# Goldfish-Voiceboard-based_on_fishr3.net
KiCad netlist of a schematic drawn in EAGLE
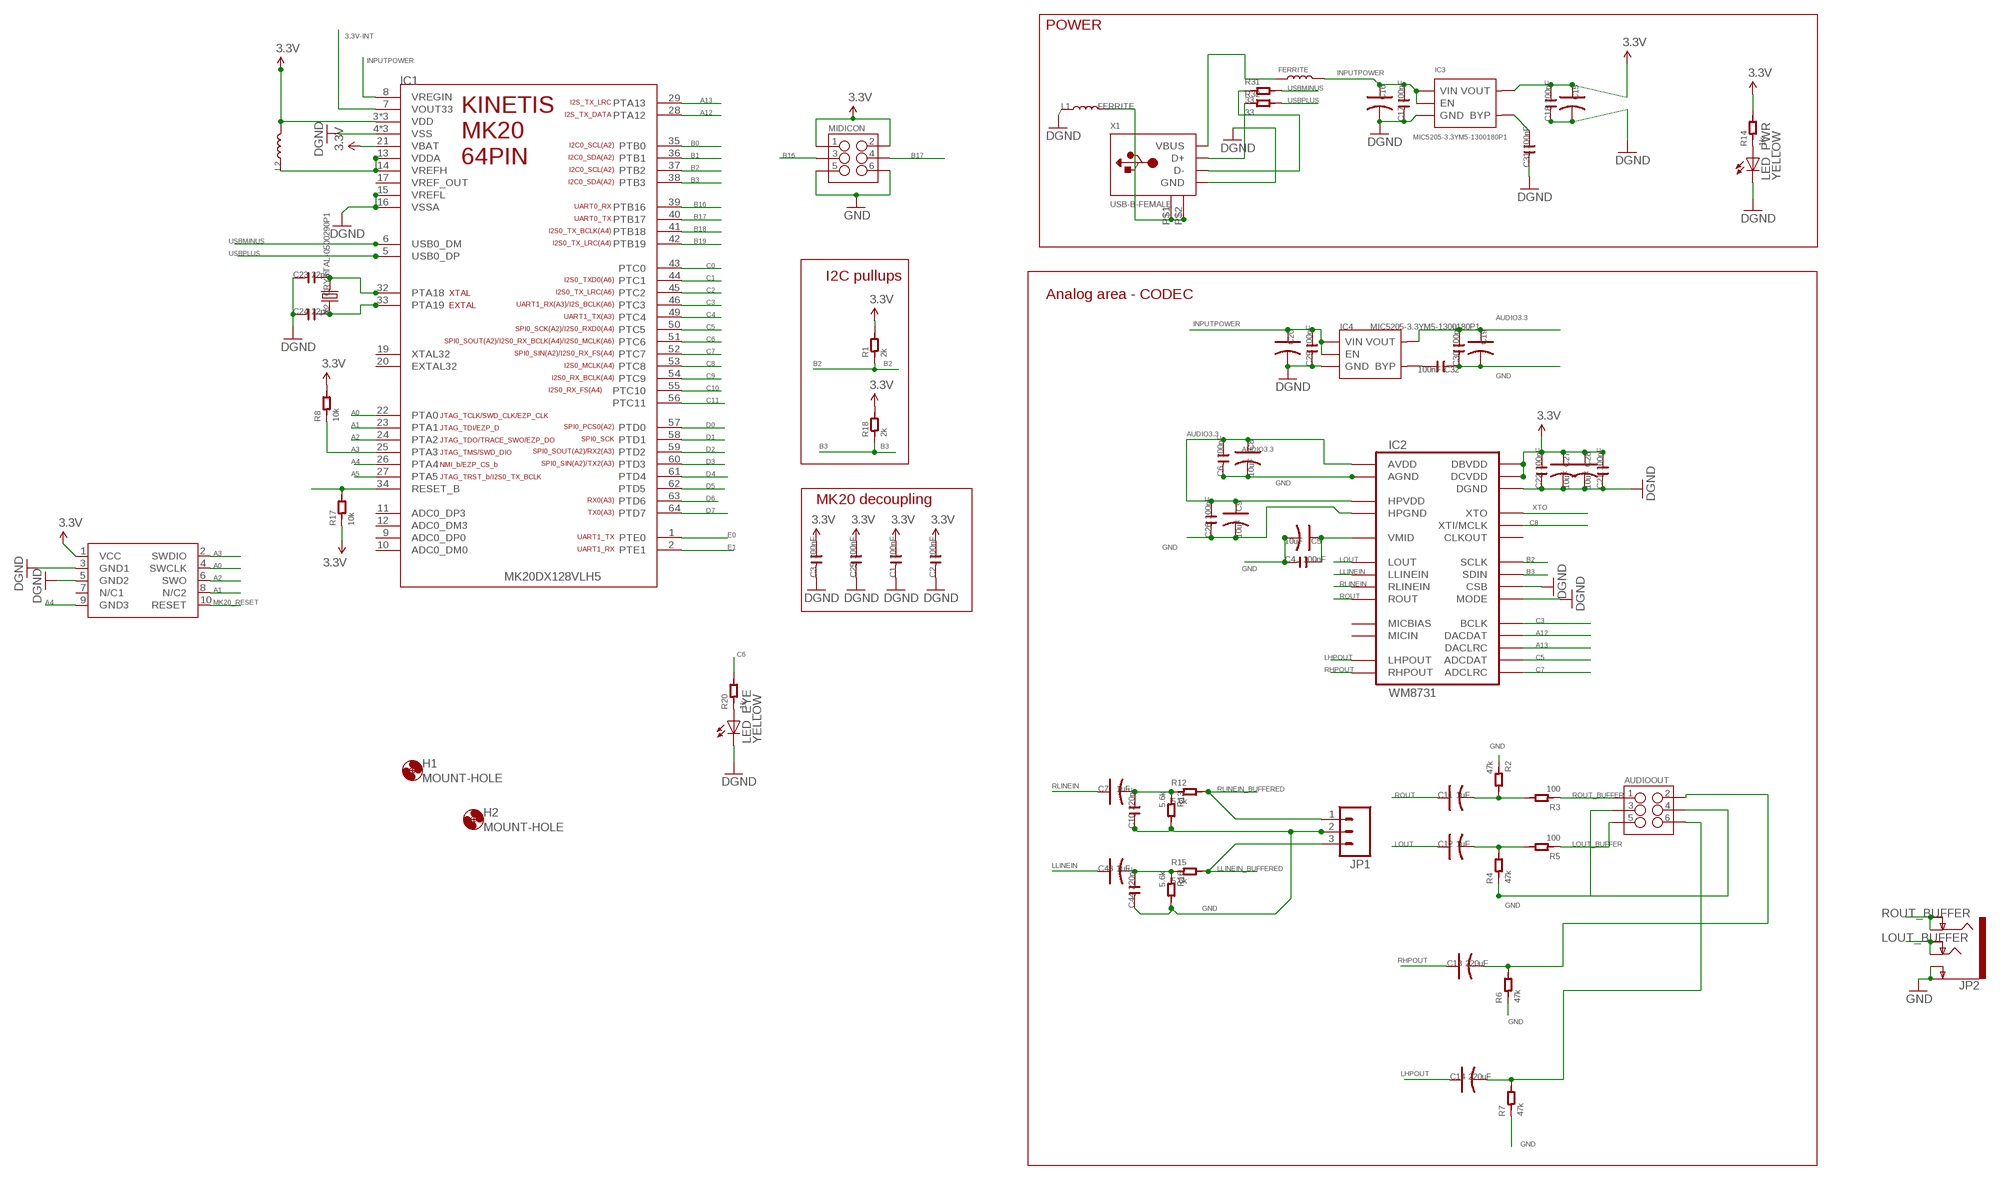
[diagram p0: schematic, sheet 1]

(export (version "E")
  (design (tool "Eeschema 10.0.6"))
  (components
    (comp (ref "AUDIOOUT")
      (value "M03X2SMT")
      (footprint "eagle-import:2X3_SMT_POSTS")
      (libsource (lib "eagle-import") (part "M03X2SMT"))
    )
    (comp (ref "C1")
      (value "100nF")
      (footprint "eagle-import:C0603")
      (libsource (lib "eagle-import") (part "C-0603"))
    )
    (comp (ref "C2")
      (value "100nF")
      (footprint "eagle-import:C0603")
      (libsource (lib "eagle-import") (part "C-0603"))
    )
    (comp (ref "C3")
      (value "100nF")
      (footprint "eagle-import:C0603")
      (libsource (lib "eagle-import") (part "C-0603"))
    )
    (comp (ref "C4")
      (value "100nF")
      (footprint "eagle-import:C0603")
      (libsource (lib "eagle-import") (part "C-0603"))
    )
    (comp (ref "C5")
      (value "10uF")
      (footprint "eagle-import:AVX-A")
      (libsource (lib "eagle-import") (part "C-POLAR-A"))
    )
    (comp (ref "C6")
      (value "100nF")
      (footprint "eagle-import:C0603")
      (libsource (lib "eagle-import") (part "C-0603"))
    )
    (comp (ref "C7")
      (value "1uF")
      (footprint "eagle-import:AVX-A")
      (libsource (lib "eagle-import") (part "C-POLAR-A"))
    )
    (comp (ref "C8")
      (value "10uF")
      (footprint "eagle-import:AVX-A")
      (libsource (lib "eagle-import") (part "C-POLAR-A"))
    )
    (comp (ref "C9")
      (value "10uF")
      (footprint "eagle-import:AVX-A")
      (libsource (lib "eagle-import") (part "C-POLAR-A"))
    )
    (comp (ref "C10")
      (value "220nF")
      (footprint "eagle-import:C0603")
      (libsource (lib "eagle-import") (part "C-0603"))
    )
    (comp (ref "C11")
      (value "1uF")
      (footprint "eagle-import:AVX-A")
      (libsource (lib "eagle-import") (part "C-POLAR-A"))
    )
    (comp (ref "C12")
      (value "1uF")
      (footprint "eagle-import:AVX-A")
      (libsource (lib "eagle-import") (part "C-POLAR-A"))
    )
    (comp (ref "C13")
      (value "220uF")
      (footprint "eagle-import:AVX-B")
      (libsource (lib "eagle-import") (part "C-POLAR-B"))
    )
    (comp (ref "C14")
      (value "220uF")
      (footprint "eagle-import:AVX-B")
      (libsource (lib "eagle-import") (part "C-POLAR-B"))
    )
    (comp (ref "C15")
      (value "C-POLAR-A")
      (footprint "eagle-import:AVX-A")
      (libsource (lib "eagle-import") (part "C-POLAR-A"))
    )
    (comp (ref "C16")
      (value "C-POLAR-A")
      (footprint "eagle-import:AVX-A")
      (libsource (lib "eagle-import") (part "C-POLAR-A"))
    )
    (comp (ref "C17")
      (value "100nF")
      (footprint "eagle-import:C0603")
      (libsource (lib "eagle-import") (part "C-0603"))
    )
    (comp (ref "C18")
      (value "100nF")
      (footprint "eagle-import:C0603")
      (libsource (lib "eagle-import") (part "C-0603"))
    )
    (comp (ref "C19")
      (value "C-POLAR-A")
      (footprint "eagle-import:AVX-A")
      (libsource (lib "eagle-import") (part "C-POLAR-A"))
    )
    (comp (ref "C20")
      (value "C-POLAR-A")
      (footprint "eagle-import:AVX-A")
      (libsource (lib "eagle-import") (part "C-POLAR-A"))
    )
    (comp (ref "C21")
      (value "100nF")
      (footprint "eagle-import:C0603")
      (libsource (lib "eagle-import") (part "C-0603"))
    )
    (comp (ref "C22")
      (value "100nF")
      (footprint "eagle-import:C0603")
      (libsource (lib "eagle-import") (part "C-0603"))
    )
    (comp (ref "C23")
      (value "22pF")
      (footprint "eagle-import:C0603")
      (libsource (lib "eagle-import") (part "C-0603"))
    )
    (comp (ref "C24")
      (value "22pF")
      (footprint "eagle-import:C0603")
      (libsource (lib "eagle-import") (part "C-0603"))
    )
    (comp (ref "C25")
      (value "100nF")
      (footprint "eagle-import:C0603")
      (libsource (lib "eagle-import") (part "C-0603"))
    )
    (comp (ref "C26")
      (value "100nF")
      (footprint "eagle-import:C0603")
      (libsource (lib "eagle-import") (part "C-0603"))
    )
    (comp (ref "C27")
      (value "10uF")
      (footprint "eagle-import:AVX-A")
      (libsource (lib "eagle-import") (part "C-POLAR-A"))
    )
    (comp (ref "C28")
      (value "10uF")
      (footprint "eagle-import:AVX-A")
      (libsource (lib "eagle-import") (part "C-POLAR-A"))
    )
    (comp (ref "C29")
      (value "100nF")
      (footprint "eagle-import:C0603")
      (libsource (lib "eagle-import") (part "C-0603"))
    )
    (comp (ref "C30")
      (value "100nF")
      (footprint "eagle-import:C0603")
      (libsource (lib "eagle-import") (part "C-0603"))
    )
    (comp (ref "C31")
      (value "100nF")
      (footprint "eagle-import:C0603")
      (libsource (lib "eagle-import") (part "C-0603"))
    )
    (comp (ref "C32")
      (value "100nF")
      (footprint "eagle-import:C0603")
      (libsource (lib "eagle-import") (part "C-0603"))
    )
    (comp (ref "C43")
      (value "1uF")
      (footprint "eagle-import:AVX-A")
      (libsource (lib "eagle-import") (part "C-POLAR-A"))
    )
    (comp (ref "C44")
      (value "220nF")
      (footprint "eagle-import:C0603")
      (libsource (lib "eagle-import") (part "C-0603"))
    )
    (comp (ref "H1")
      (value "MOUNT-HOLE")
      (footprint "eagle-import:3.2-NOMARKINGS-SMALLSAFEZONE")
      (libsource (lib "eagle-import") (part "MOUNT-HOLE"))
    )
    (comp (ref "H2")
      (value "MOUNT-HOLE")
      (footprint "eagle-import:3.2-NOMARKINGS-SMALLSAFEZONE")
      (libsource (lib "eagle-import") (part "MOUNT-HOLE"))
    )
    (comp (ref "IC1")
      (value "MK20DX128VLH5")
      (footprint "eagle-import:MK20DX128VLH5")
      (libsource (lib "eagle-import") (part "MK20DX128VLH5"))
    )
    (comp (ref "IC2")
      (value "WM8731")
      (footprint "eagle-import:28-SSOP")
      (libsource (lib "eagle-import") (part "WM8731"))
    )
    (comp (ref "IC3")
      (value "MIC5205-3.3YM5-1300180P1")
      (footprint "eagle-import:SOT23-5")
      (libsource (lib "eagle-import") (part "MIC5205-3.3YM5-1300180P1"))
    )
    (comp (ref "IC4")
      (value "MIC5205-3.3YM5-1300180P1")
      (footprint "eagle-import:SOT23-5")
      (libsource (lib "eagle-import") (part "MIC5205-3.3YM5-1300180P1"))
    )
    (comp (ref "JP1")
      (value "M03PTH")
      (footprint "eagle-import:1X03")
      (libsource (lib "eagle-import") (part "M03PTH"))
    )
    (comp (ref "JP2")
      (value "AUDIO-JACK4-.25-HORIZ-TRS")
      (footprint "eagle-import:AUDIO-JACK-.25-INCH-HORIZ-PTH")
      (libsource (lib "eagle-import") (part "AUDIO-JACK4-.25-HORIZ-TRS"))
    )
    (comp (ref "L1")
      (value "FERRITE")
      (footprint "eagle-import:L0603")
      (libsource (lib "eagle-import") (part "L-0603"))
    )
    (comp (ref "L2")
      (value "L-0603")
      (footprint "eagle-import:L0603")
      (libsource (lib "eagle-import") (part "L-0603"))
    )
    (comp (ref "L4")
      (value "FERRITE")
      (footprint "eagle-import:L0603")
      (libsource (lib "eagle-import") (part "L-0603"))
    )
    (comp (ref "LED_EYE")
      (value "YELLOW")
      (footprint "eagle-import:CHIP-LED0603")
      (libsource (lib "eagle-import") (part "LEDCHIP-LED0603"))
    )
    (comp (ref "LED_PWR")
      (value "YELLOW")
      (footprint "eagle-import:CHIP-LED0603")
      (libsource (lib "eagle-import") (part "LEDCHIP-LED0603"))
    )
    (comp (ref "MIDICON")
      (value "M03X2SMT")
      (footprint "eagle-import:2X3_SMT_POSTS")
      (libsource (lib "eagle-import") (part "M03X2SMT"))
    )
    (comp (ref "R1")
      (value "2k")
      (footprint "eagle-import:R0603")
      (libsource (lib "eagle-import") (part "R-0603"))
    )
    (comp (ref "R2")
      (value "47k")
      (footprint "eagle-import:R0603")
      (libsource (lib "eagle-import") (part "OPL Eagle Library_R-0603"))
    )
    (comp (ref "R3")
      (value "100")
      (footprint "eagle-import:R0603")
      (libsource (lib "eagle-import") (part "OPL Eagle Library_R-0603"))
    )
    (comp (ref "R4")
      (value "47k")
      (footprint "eagle-import:R0603")
      (libsource (lib "eagle-import") (part "OPL Eagle Library_R-0603"))
    )
    (comp (ref "R5")
      (value "100")
      (footprint "eagle-import:R0603")
      (libsource (lib "eagle-import") (part "OPL Eagle Library_R-0603"))
    )
    (comp (ref "R6")
      (value "47k")
      (footprint "eagle-import:R0603")
      (libsource (lib "eagle-import") (part "OPL Eagle Library_R-0603"))
    )
    (comp (ref "R7")
      (value "47k")
      (footprint "eagle-import:R0603")
      (libsource (lib "eagle-import") (part "OPL Eagle Library_R-0603"))
    )
    (comp (ref "R8")
      (value "10k")
      (footprint "eagle-import:R0603")
      (libsource (lib "eagle-import") (part "OPL Eagle Library_R-0603"))
    )
    (comp (ref "R12")
      (value "5.6k")
      (footprint "eagle-import:R0603")
      (libsource (lib "eagle-import") (part "OPL Eagle Library_R-0603"))
    )
    (comp (ref "R13")
      (value "5.6k")
      (footprint "eagle-import:R0603")
      (libsource (lib "eagle-import") (part "OPL Eagle Library_R-0603"))
    )
    (comp (ref "R14")
      (value "1k")
      (footprint "eagle-import:R0603")
      (libsource (lib "eagle-import") (part "OPL Eagle Library_R-0603"))
    )
    (comp (ref "R15")
      (value "5.6k")
      (footprint "eagle-import:R0603")
      (libsource (lib "eagle-import") (part "OPL Eagle Library_R-0603"))
    )
    (comp (ref "R16")
      (value "5.6k")
      (footprint "eagle-import:R0603")
      (libsource (lib "eagle-import") (part "OPL Eagle Library_R-0603"))
    )
    (comp (ref "R17")
      (value "10k")
      (footprint "eagle-import:R0603")
      (libsource (lib "eagle-import") (part "OPL Eagle Library_R-0603"))
    )
    (comp (ref "R18")
      (value "2k")
      (footprint "eagle-import:R0603")
      (libsource (lib "eagle-import") (part "R-0603"))
    )
    (comp (ref "R20")
      (value "1k")
      (footprint "eagle-import:R0603")
      (libsource (lib "eagle-import") (part "OPL Eagle Library_R-0603"))
    )
    (comp (ref "R31")
      (value "33")
      (footprint "eagle-import:R0603")
      (libsource (lib "eagle-import") (part "OPL Eagle Library_R-0603"))
    )
    (comp (ref "R32")
      (value "33")
      (footprint "eagle-import:R0603")
      (libsource (lib "eagle-import") (part "OPL Eagle Library_R-0603"))
    )
    (comp (ref "SWD1")
      (value "CORTEX_SWD")
      (footprint "eagle-import:M50-3600542")
      (libsource (lib "eagle-import") (part "CORTEX_SWD"))
    )
    (comp (ref "X1")
      (value "USB-B-FEMALE")
      (footprint "eagle-import:FCI61729")
      (libsource (lib "eagle-import") (part "USB-B-FEMALE"))
    )
    (comp (ref "X2")
      (value "CRYSTAL-0500290P1")
      (footprint "eagle-import:2P-SMD-5.0X3.2")
      (libsource (lib "eagle-import") (part "CRYSTAL-0500290P1"))
    )
  )
  (nets
    (net (code "1") (name "/3.3V-INT") (class "Default")
      (node (ref "IC1") (pin "7") (pinfunction "VOUT33_7") (pintype "bidirectional"))
    )
    (net (code "2") (name "/A0") (class "Default")
      (node (ref "IC1") (pin "22") (pinfunction "PTA0_22") (pintype "bidirectional"))
      (node (ref "SWD1") (pin "4") (pinfunction "SWCLK_4") (pintype "bidirectional"))
    )
    (net (code "3") (name "/A1") (class "Default")
      (node (ref "IC1") (pin "23") (pinfunction "PTA1_23") (pintype "bidirectional"))
      (node (ref "SWD1") (pin "8") (pinfunction "N/C2_8") (pintype "bidirectional"))
    )
    (net (code "4") (name "/A2") (class "Default")
      (node (ref "IC1") (pin "24") (pinfunction "PTA2_24") (pintype "bidirectional"))
      (node (ref "SWD1") (pin "6") (pinfunction "SWO_6") (pintype "bidirectional"))
    )
    (net (code "5") (name "/A3") (class "Default")
      (node (ref "IC1") (pin "25") (pinfunction "PTA3_25") (pintype "bidirectional"))
      (node (ref "R8") (pin "1") (pinfunction "1_1") (pintype "bidirectional"))
      (node (ref "SWD1") (pin "2") (pinfunction "SWDIO_2") (pintype "bidirectional"))
    )
    (net (code "6") (name "/A4") (class "Default")
      (node (ref "IC1") (pin "26") (pinfunction "PTA4_26") (pintype "bidirectional"))
      (node (ref "SWD1") (pin "9") (pinfunction "GND3_9") (pintype "bidirectional"))
    )
    (net (code "7") (name "/A5") (class "Default")
      (node (ref "IC1") (pin "27") (pinfunction "PTA5_27") (pintype "bidirectional"))
    )
    (net (code "8") (name "/A12") (class "Default")
      (node (ref "IC1") (pin "28") (pinfunction "PTA12_28") (pintype "bidirectional"))
      (node (ref "IC2") (pin "P$4") (pinfunction "DACDAT_P$4") (pintype "input"))
    )
    (net (code "9") (name "/A13") (class "Default")
      (node (ref "IC1") (pin "29") (pinfunction "PTA13_29") (pintype "bidirectional"))
      (node (ref "IC2") (pin "P$5") (pinfunction "DACLRC_P$5") (pintype "bidirectional"))
    )
    (net (code "10") (name "/AUDIO3.3") (class "Default")
      (node (ref "C19") (pin "+") (pinfunction "1_+") (pintype "bidirectional"))
      (node (ref "C26") (pin "2") (pinfunction "2_2") (pintype "bidirectional"))
      (node (ref "C30") (pin "2") (pinfunction "2_2") (pintype "bidirectional"))
      (node (ref "C6") (pin "2") (pinfunction "2_2") (pintype "bidirectional"))
      (node (ref "C8") (pin "+") (pinfunction "1_+") (pintype "bidirectional"))
      (node (ref "C9") (pin "+") (pinfunction "1_+") (pintype "bidirectional"))
      (node (ref "IC2") (pin "P$14") (pinfunction "AVDD_P$14") (pintype "power_in"))
      (node (ref "IC2") (pin "P$8") (pinfunction "HPVDD_P$8") (pintype "power_in"))
      (node (ref "IC4") (pin "5") (pinfunction "VOUT_5") (pintype "bidirectional"))
    )
    (net (code "11") (name "/B0") (class "Default")
      (node (ref "IC1") (pin "35") (pinfunction "PTB0_35") (pintype "bidirectional"))
    )
    (net (code "12") (name "/B1") (class "Default")
      (node (ref "IC1") (pin "36") (pinfunction "PTB1_36") (pintype "bidirectional"))
    )
    (net (code "13") (name "/B2") (class "Default")
      (node (ref "IC1") (pin "37") (pinfunction "PTB2_37") (pintype "bidirectional"))
      (node (ref "IC2") (pin "P$24") (pinfunction "SCLK_P$24") (pintype "input"))
      (node (ref "R1") (pin "1") (pinfunction "1_1") (pintype "bidirectional"))
    )
    (net (code "14") (name "/B3") (class "Default")
      (node (ref "IC1") (pin "38") (pinfunction "PTB3_38") (pintype "bidirectional"))
      (node (ref "IC2") (pin "P$23") (pinfunction "SDIN_P$23") (pintype "bidirectional"))
      (node (ref "R18") (pin "1") (pinfunction "1_1") (pintype "bidirectional"))
    )
    (net (code "15") (name "/B16") (class "Default")
      (node (ref "IC1") (pin "39") (pinfunction "PTB16_39") (pintype "bidirectional"))
      (node (ref "MIDICON") (pin "3") (pinfunction "3_3") (pintype "bidirectional"))
    )
    (net (code "16") (name "/B17") (class "Default")
      (node (ref "IC1") (pin "40") (pinfunction "PTB17_40") (pintype "bidirectional"))
      (node (ref "MIDICON") (pin "4") (pinfunction "4_4") (pintype "bidirectional"))
    )
    (net (code "17") (name "/B18") (class "Default")
      (node (ref "IC1") (pin "41") (pinfunction "PTB18_41") (pintype "bidirectional"))
    )
    (net (code "18") (name "/B19") (class "Default")
      (node (ref "IC1") (pin "42") (pinfunction "PTB19_42") (pintype "bidirectional"))
    )
    (net (code "19") (name "/C0") (class "Default")
      (node (ref "IC1") (pin "43") (pinfunction "PTC0_43") (pintype "bidirectional"))
    )
    (net (code "20") (name "/C1") (class "Default")
      (node (ref "IC1") (pin "44") (pinfunction "PTC1_44") (pintype "bidirectional"))
    )
    (net (code "21") (name "/C2") (class "Default")
      (node (ref "IC1") (pin "45") (pinfunction "PTC2_45") (pintype "bidirectional"))
    )
    (net (code "22") (name "/C3") (class "Default")
      (node (ref "IC1") (pin "46") (pinfunction "PTC3_46") (pintype "bidirectional"))
      (node (ref "IC2") (pin "P$3") (pinfunction "BCLK_P$3") (pintype "bidirectional"))
    )
    (net (code "23") (name "/C4") (class "Default")
      (node (ref "IC1") (pin "49") (pinfunction "PTC4_49") (pintype "bidirectional"))
    )
    (net (code "24") (name "/C5") (class "Default")
      (node (ref "IC1") (pin "50") (pinfunction "PTC5_50") (pintype "bidirectional"))
      (node (ref "IC2") (pin "P$6") (pinfunction "ADCDAT_P$6") (pintype "output"))
    )
    (net (code "25") (name "/C6") (class "Default")
      (node (ref "IC1") (pin "51") (pinfunction "PTC6_51") (pintype "bidirectional"))
      (node (ref "R20") (pin "2") (pinfunction "2_2") (pintype "bidirectional"))
    )
    (net (code "26") (name "/C7") (class "Default")
      (node (ref "IC1") (pin "52") (pinfunction "PTC7_52") (pintype "bidirectional"))
      (node (ref "IC2") (pin "P$7") (pinfunction "ADCLRC_P$7") (pintype "bidirectional"))
    )
    (net (code "27") (name "/C8") (class "Default")
      (node (ref "IC1") (pin "53") (pinfunction "PTC8_53") (pintype "bidirectional"))
      (node (ref "IC2") (pin "P$25") (pinfunction "XTI/MCLK_P$25") (pintype "input"))
    )
    (net (code "28") (name "/C9") (class "Default")
      (node (ref "IC1") (pin "54") (pinfunction "PTC9_54") (pintype "bidirectional"))
    )
    (net (code "29") (name "/C10") (class "Default")
      (node (ref "IC1") (pin "55") (pinfunction "PTC10_55") (pintype "bidirectional"))
    )
    (net (code "30") (name "/C11") (class "Default")
      (node (ref "IC1") (pin "56") (pinfunction "PTC11_56") (pintype "bidirectional"))
    )
    (net (code "31") (name "/D0") (class "Default")
      (node (ref "IC1") (pin "57") (pinfunction "PTD0_57") (pintype "bidirectional"))
    )
    (net (code "32") (name "/D1") (class "Default")
      (node (ref "IC1") (pin "58") (pinfunction "PTD1_58") (pintype "bidirectional"))
    )
    (net (code "33") (name "/D2") (class "Default")
      (node (ref "IC1") (pin "59") (pinfunction "PTD2_59") (pintype "bidirectional"))
    )
    (net (code "34") (name "/D3") (class "Default")
      (node (ref "IC1") (pin "60") (pinfunction "PTD3_60") (pintype "bidirectional"))
    )
    (net (code "35") (name "/D4") (class "Default")
      (node (ref "IC1") (pin "61") (pinfunction "PTD4_61") (pintype "bidirectional"))
    )
    (net (code "36") (name "/D5") (class "Default")
      (node (ref "IC1") (pin "62") (pinfunction "PTD5_62") (pintype "bidirectional"))
    )
    (net (code "37") (name "/D6") (class "Default")
      (node (ref "IC1") (pin "63") (pinfunction "PTD6_63") (pintype "bidirectional"))
    )
    (net (code "38") (name "/D7") (class "Default")
      (node (ref "IC1") (pin "64") (pinfunction "PTD7_64") (pintype "bidirectional"))
    )
    (net (code "39") (name "/E0") (class "Default")
      (node (ref "IC1") (pin "1") (pinfunction "PTE0_1") (pintype "bidirectional"))
    )
    (net (code "40") (name "/E1") (class "Default")
      (node (ref "IC1") (pin "2") (pinfunction "PTE1_2") (pintype "bidirectional"))
    )
    (net (code "41") (name "/INPUTPOWER") (class "Default")
      (node (ref "C16") (pin "+") (pinfunction "1_+") (pintype "bidirectional"))
      (node (ref "C17") (pin "2") (pinfunction "2_2") (pintype "bidirectional"))
      (node (ref "C20") (pin "+") (pinfunction "1_+") (pintype "bidirectional"))
      (node (ref "C29") (pin "2") (pinfunction "2_2") (pintype "bidirectional"))
      (node (ref "IC1") (pin "8") (pinfunction "VREGIN_8") (pintype "bidirectional"))
      (node (ref "IC3") (pin "1") (pinfunction "VIN_1") (pintype "bidirectional"))
      (node (ref "IC3") (pin "3") (pinfunction "EN_3") (pintype "bidirectional"))
      (node (ref "IC4") (pin "1") (pinfunction "VIN_1") (pintype "bidirectional"))
      (node (ref "IC4") (pin "3") (pinfunction "EN_3") (pintype "bidirectional"))
      (node (ref "L4") (pin "2") (pinfunction "2_2") (pintype "passive"))
    )
    (net (code "42") (name "/LHPOUT") (class "Default")
      (node (ref "C14") (pin "+") (pinfunction "1_+") (pintype "bidirectional"))
      (node (ref "IC2") (pin "P$9") (pinfunction "LHPOUT_P$9") (pintype "output"))
    )
    (net (code "43") (name "/LLINEIN") (class "Default")
      (node (ref "C43") (pin "+") (pinfunction "1_+") (pintype "bidirectional"))
      (node (ref "IC2") (pin "P$20") (pinfunction "LLINEIN_P$20") (pintype "input"))
    )
    (net (code "44") (name "/LLINEIN_BUFFERED") (class "Default")
      (node (ref "JP1") (pin "3") (pinfunction "3_3") (pintype "passive"))
      (node (ref "R15") (pin "2") (pinfunction "2_2") (pintype "bidirectional"))
    )
    (net (code "45") (name "/LOUT") (class "Default")
      (node (ref "C12") (pin "+") (pinfunction "1_+") (pintype "bidirectional"))
      (node (ref "IC2") (pin "P$12") (pinfunction "LOUT_P$12") (pintype "output"))
    )
    (net (code "46") (name "/LOUT_BUFFER") (class "Default")
      (node (ref "AUDIOOUT") (pin "5") (pinfunction "5_5") (pintype "bidirectional"))
      (node (ref "JP2") (pin "P$6") (pinfunction "TIP_P$6") (pintype "bidirectional"))
      (node (ref "JP2") (pin "P$7") (pinfunction "TIP-NORM_P$7") (pintype "bidirectional"))
      (node (ref "R5") (pin "1") (pinfunction "1_1") (pintype "bidirectional"))
    )
    (net (code "47") (name "/MK20_RESET") (class "Default")
      (node (ref "IC1") (pin "34") (pinfunction "RESET_B_34") (pintype "bidirectional"))
      (node (ref "R17") (pin "2") (pinfunction "2_2") (pintype "bidirectional"))
      (node (ref "SWD1") (pin "10") (pinfunction "RESET_10") (pintype "bidirectional"))
    )
    (net (code "48") (name "/RHPOUT") (class "Default")
      (node (ref "C13") (pin "+") (pinfunction "1_+") (pintype "bidirectional"))
      (node (ref "IC2") (pin "P$10") (pinfunction "RHPOUT_P$10") (pintype "output"))
    )
    (net (code "49") (name "/RLINEIN") (class "Default")
      (node (ref "C7") (pin "+") (pinfunction "1_+") (pintype "bidirectional"))
      (node (ref "IC2") (pin "P$19") (pinfunction "RLINEIN_P$19") (pintype "input"))
    )
    (net (code "50") (name "/RLINEIN_BUFFERED") (class "Default")
      (node (ref "JP1") (pin "1") (pinfunction "1_1") (pintype "passive"))
      (node (ref "R12") (pin "2") (pinfunction "2_2") (pintype "bidirectional"))
    )
    (net (code "51") (name "/ROUT") (class "Default")
      (node (ref "C11") (pin "+") (pinfunction "1_+") (pintype "bidirectional"))
      (node (ref "IC2") (pin "P$13") (pinfunction "ROUT_P$13") (pintype "output"))
    )
    (net (code "52") (name "/ROUT_BUFFER") (class "Default")
      (node (ref "AUDIOOUT") (pin "1") (pinfunction "1_1") (pintype "bidirectional"))
      (node (ref "JP2") (pin "P$4") (pinfunction "RING_P$4") (pintype "bidirectional"))
      (node (ref "JP2") (pin "P$5") (pinfunction "RING-NORM_P$5") (pintype "bidirectional"))
      (node (ref "R3") (pin "1") (pinfunction "1_1") (pintype "bidirectional"))
    )
    (net (code "53") (name "/USBMINUS") (class "Default")
      (node (ref "IC1") (pin "6") (pinfunction "USB0_DM_6") (pintype "bidirectional"))
      (node (ref "R31") (pin "2") (pinfunction "2_2") (pintype "bidirectional"))
    )
    (net (code "54") (name "/USBPLUS") (class "Default")
      (node (ref "IC1") (pin "5") (pinfunction "USB0_DP_5") (pintype "bidirectional"))
      (node (ref "R32") (pin "2") (pinfunction "2_2") (pintype "bidirectional"))
    )
    (net (code "55") (name "/XTO") (class "Default")
      (node (ref "IC2") (pin "P$26") (pinfunction "XTO_P$26") (pintype "output"))
    )
    (net (code "56") (name "3.3V") (class "Default")
      (node (ref "C1") (pin "2") (pinfunction "2_2") (pintype "bidirectional"))
      (node (ref "C15") (pin "+") (pinfunction "1_+") (pintype "bidirectional"))
      (node (ref "C18") (pin "2") (pinfunction "2_2") (pintype "bidirectional"))
      (node (ref "C2") (pin "2") (pinfunction "2_2") (pintype "bidirectional"))
      (node (ref "C21") (pin "2") (pinfunction "2_2") (pintype "bidirectional"))
      (node (ref "C22") (pin "2") (pinfunction "2_2") (pintype "bidirectional"))
      (node (ref "C25") (pin "2") (pinfunction "2_2") (pintype "bidirectional"))
      (node (ref "C27") (pin "+") (pinfunction "1_+") (pintype "bidirectional"))
      (node (ref "C28") (pin "+") (pinfunction "1_+") (pintype "bidirectional"))
      (node (ref "C3") (pin "2") (pinfunction "2_2") (pintype "bidirectional"))
      (node (ref "IC1") (pin "21") (pinfunction "VBAT_21") (pintype "bidirectional"))
      (node (ref "IC1") (pin "3") (pinfunction "VDD_3") (pintype "bidirectional"))
      (node (ref "IC1") (pin "30") (pinfunction "VDD_30") (pintype "bidirectional"))
      (node (ref "IC1") (pin "48") (pinfunction "VDD_48") (pintype "bidirectional"))
      (node (ref "IC2") (pin "P$1") (pinfunction "DBVDD_P$1") (pintype "power_in"))
      (node (ref "IC2") (pin "P$27") (pinfunction "DCVDD_P$27") (pintype "power_in"))
      (node (ref "IC3") (pin "5") (pinfunction "VOUT_5") (pintype "bidirectional"))
      (node (ref "L2") (pin "2") (pinfunction "2_2") (pintype "passive"))
      (node (ref "MIDICON") (pin "1") (pinfunction "1_1") (pintype "bidirectional"))
      (node (ref "MIDICON") (pin "2") (pinfunction "2_2") (pintype "bidirectional"))
      (node (ref "R1") (pin "2") (pinfunction "2_2") (pintype "bidirectional"))
      (node (ref "R14") (pin "2") (pinfunction "2_2") (pintype "bidirectional"))
      (node (ref "R17") (pin "1") (pinfunction "1_1") (pintype "bidirectional"))
      (node (ref "R18") (pin "2") (pinfunction "2_2") (pintype "bidirectional"))
      (node (ref "R8") (pin "2") (pinfunction "2_2") (pintype "bidirectional"))
      (node (ref "SWD1") (pin "1") (pinfunction "VCC_1") (pintype "bidirectional"))
    )
    (net (code "57") (name "DGND") (class "Default")
      (node (ref "AUDIOOUT") (pin "3") (pinfunction "3_3") (pintype "bidirectional"))
      (node (ref "AUDIOOUT") (pin "4") (pinfunction "4_4") (pintype "bidirectional"))
      (node (ref "C1") (pin "1") (pinfunction "1_1") (pintype "bidirectional"))
      (node (ref "C10") (pin "1") (pinfunction "1_1") (pintype "bidirectional"))
      (node (ref "C15") (pin "-") (pinfunction "2_-") (pintype "bidirectional"))
      (node (ref "C16") (pin "-") (pinfunction "2_-") (pintype "bidirectional"))
      (node (ref "C17") (pin "1") (pinfunction "1_1") (pintype "bidirectional"))
      (node (ref "C18") (pin "1") (pinfunction "1_1") (pintype "bidirectional"))
      (node (ref "C19") (pin "-") (pinfunction "2_-") (pintype "bidirectional"))
      (node (ref "C2") (pin "1") (pinfunction "1_1") (pintype "bidirectional"))
      (node (ref "C20") (pin "-") (pinfunction "2_-") (pintype "bidirectional"))
      (node (ref "C21") (pin "1") (pinfunction "1_1") (pintype "bidirectional"))
      (node (ref "C22") (pin "1") (pinfunction "1_1") (pintype "bidirectional"))
      (node (ref "C23") (pin "1") (pinfunction "1_1") (pintype "bidirectional"))
      (node (ref "C24") (pin "1") (pinfunction "1_1") (pintype "bidirectional"))
      (node (ref "C25") (pin "1") (pinfunction "1_1") (pintype "bidirectional"))
      (node (ref "C26") (pin "1") (pinfunction "1_1") (pintype "bidirectional"))
      (node (ref "C27") (pin "-") (pinfunction "2_-") (pintype "bidirectional"))
      (node (ref "C28") (pin "-") (pinfunction "2_-") (pintype "bidirectional"))
      (node (ref "C29") (pin "1") (pinfunction "1_1") (pintype "bidirectional"))
      (node (ref "C3") (pin "1") (pinfunction "1_1") (pintype "bidirectional"))
      (node (ref "C30") (pin "1") (pinfunction "1_1") (pintype "bidirectional"))
      (node (ref "C31") (pin "1") (pinfunction "1_1") (pintype "bidirectional"))
      (node (ref "C32") (pin "1") (pinfunction "1_1") (pintype "bidirectional"))
      (node (ref "C4") (pin "1") (pinfunction "1_1") (pintype "bidirectional"))
      (node (ref "C44") (pin "1") (pinfunction "1_1") (pintype "bidirectional"))
      (node (ref "C5") (pin "-") (pinfunction "2_-") (pintype "bidirectional"))
      (node (ref "C6") (pin "1") (pinfunction "1_1") (pintype "bidirectional"))
      (node (ref "C8") (pin "-") (pinfunction "2_-") (pintype "bidirectional"))
      (node (ref "C9") (pin "-") (pinfunction "2_-") (pintype "bidirectional"))
      (node (ref "IC1") (pin "15") (pinfunction "VREFL_15") (pintype "bidirectional"))
      (node (ref "IC1") (pin "16") (pinfunction "VSSA_16") (pintype "bidirectional"))
      (node (ref "IC1") (pin "31") (pinfunction "VSS_31") (pintype "bidirectional"))
      (node (ref "IC1") (pin "4") (pinfunction "VSS_4") (pintype "bidirectional"))
      (node (ref "IC1") (pin "47") (pinfunction "VSS_47") (pintype "bidirectional"))
      (node (ref "IC2") (pin "P$11") (pinfunction "HPGND_P$11") (pintype "power_in"))
      (node (ref "IC2") (pin "P$15") (pinfunction "AGND_P$15") (pintype "power_in"))
      (node (ref "IC2") (pin "P$21") (pinfunction "MODE_P$21") (pintype "input"))
      (node (ref "IC2") (pin "P$22") (pinfunction "CSB_P$22") (pintype "input"))
      (node (ref "IC2") (pin "P$28") (pinfunction "DGND_P$28") (pintype "power_in"))
      (node (ref "IC3") (pin "2") (pinfunction "GND_2") (pintype "bidirectional"))
      (node (ref "IC4") (pin "2") (pinfunction "GND_2") (pintype "bidirectional"))
      (node (ref "JP1") (pin "2") (pinfunction "2_2") (pintype "passive"))
      (node (ref "JP2") (pin "P$2") (pinfunction "EARTH_P$2") (pintype "bidirectional"))
      (node (ref "JP2") (pin "P$3") (pinfunction "EARTH-NORM_P$3") (pintype "bidirectional"))
      (node (ref "L1") (pin "1") (pinfunction "1_1") (pintype "passive"))
      (node (ref "LED_EYE") (pin "C") (pinfunction "C_C") (pintype "passive"))
      (node (ref "LED_PWR") (pin "C") (pinfunction "C_C") (pintype "passive"))
      (node (ref "MIDICON") (pin "5") (pinfunction "5_5") (pintype "bidirectional"))
      (node (ref "MIDICON") (pin "6") (pinfunction "6_6") (pintype "bidirectional"))
      (node (ref "R13") (pin "2") (pinfunction "2_2") (pintype "bidirectional"))
      (node (ref "R16") (pin "2") (pinfunction "2_2") (pintype "bidirectional"))
      (node (ref "R2") (pin "1") (pinfunction "1_1") (pintype "bidirectional"))
      (node (ref "R4") (pin "1") (pinfunction "1_1") (pintype "bidirectional"))
      (node (ref "R6") (pin "1") (pinfunction "1_1") (pintype "bidirectional"))
      (node (ref "R7") (pin "1") (pinfunction "1_1") (pintype "bidirectional"))
      (node (ref "SWD1") (pin "3") (pinfunction "GND1_3") (pintype "bidirectional"))
      (node (ref "SWD1") (pin "5") (pinfunction "GND2_5") (pintype "bidirectional"))
      (node (ref "X1") (pin "4") (pinfunction "GND_4") (pintype "power_in"))
    )
    (net (code "58") (name "Net-(C5-1)") (class "Default")
      (node (ref "C4") (pin "2") (pinfunction "2_2") (pintype "bidirectional"))
      (node (ref "C5") (pin "+") (pinfunction "1_+") (pintype "bidirectional"))
      (node (ref "IC2") (pin "P$16") (pinfunction "VMID_P$16") (pintype "output"))
    )
    (net (code "59") (name "Net-(C7-2)") (class "Default")
      (node (ref "C10") (pin "2") (pinfunction "2_2") (pintype "bidirectional"))
      (node (ref "C7") (pin "-") (pinfunction "2_-") (pintype "bidirectional"))
      (node (ref "R12") (pin "1") (pinfunction "1_1") (pintype "bidirectional"))
      (node (ref "R13") (pin "1") (pinfunction "1_1") (pintype "bidirectional"))
    )
    (net (code "60") (name "Net-(C11-2)") (class "Default")
      (node (ref "C11") (pin "-") (pinfunction "2_-") (pintype "bidirectional"))
      (node (ref "R2") (pin "2") (pinfunction "2_2") (pintype "bidirectional"))
      (node (ref "R3") (pin "2") (pinfunction "2_2") (pintype "bidirectional"))
    )
    (net (code "61") (name "Net-(C12-2)") (class "Default")
      (node (ref "C12") (pin "-") (pinfunction "2_-") (pintype "bidirectional"))
      (node (ref "R4") (pin "2") (pinfunction "2_2") (pintype "bidirectional"))
      (node (ref "R5") (pin "2") (pinfunction "2_2") (pintype "bidirectional"))
    )
    (net (code "62") (name "Net-(C13-2)") (class "Default")
      (node (ref "AUDIOOUT") (pin "2") (pinfunction "2_2") (pintype "bidirectional"))
      (node (ref "C13") (pin "-") (pinfunction "2_-") (pintype "bidirectional"))
      (node (ref "R6") (pin "2") (pinfunction "2_2") (pintype "bidirectional"))
    )
    (net (code "63") (name "Net-(C14-2)") (class "Default")
      (node (ref "AUDIOOUT") (pin "6") (pinfunction "6_6") (pintype "bidirectional"))
      (node (ref "C14") (pin "-") (pinfunction "2_-") (pintype "bidirectional"))
      (node (ref "R7") (pin "2") (pinfunction "2_2") (pintype "bidirectional"))
    )
    (net (code "64") (name "Net-(C43-2)") (class "Default")
      (node (ref "C43") (pin "-") (pinfunction "2_-") (pintype "bidirectional"))
      (node (ref "C44") (pin "2") (pinfunction "2_2") (pintype "bidirectional"))
      (node (ref "R15") (pin "1") (pinfunction "1_1") (pintype "bidirectional"))
      (node (ref "R16") (pin "1") (pinfunction "1_1") (pintype "bidirectional"))
    )
    (net (code "65") (name "Net-(IC1-PTA18)") (class "Default")
      (node (ref "C23") (pin "2") (pinfunction "2_2") (pintype "bidirectional"))
      (node (ref "IC1") (pin "32") (pinfunction "PTA18_32") (pintype "bidirectional"))
      (node (ref "X2") (pin "2") (pinfunction "2_2") (pintype "passive"))
    )
    (net (code "66") (name "Net-(IC1-PTA19)") (class "Default")
      (node (ref "C24") (pin "2") (pinfunction "2_2") (pintype "bidirectional"))
      (node (ref "IC1") (pin "33") (pinfunction "PTA19_33") (pintype "bidirectional"))
      (node (ref "X2") (pin "1") (pinfunction "1_1") (pintype "passive"))
    )
    (net (code "67") (name "Net-(IC1-VDDA)") (class "Default")
      (node (ref "IC1") (pin "13") (pinfunction "VDDA_13") (pintype "bidirectional"))
      (node (ref "IC1") (pin "14") (pinfunction "VREFH_14") (pintype "bidirectional"))
      (node (ref "L2") (pin "1") (pinfunction "1_1") (pintype "passive"))
    )
    (net (code "68") (name "Net-(IC3-BYP)") (class "Default")
      (node (ref "C31") (pin "2") (pinfunction "2_2") (pintype "bidirectional"))
      (node (ref "IC3") (pin "4") (pinfunction "BYP_4") (pintype "bidirectional"))
    )
    (net (code "69") (name "Net-(IC4-BYP)") (class "Default")
      (node (ref "C32") (pin "2") (pinfunction "2_2") (pintype "bidirectional"))
      (node (ref "IC4") (pin "4") (pinfunction "BYP_4") (pintype "bidirectional"))
    )
    (net (code "70") (name "Net-(LED_EYE-PadA)") (class "Default")
      (node (ref "LED_EYE") (pin "A") (pinfunction "A_A") (pintype "passive"))
      (node (ref "R20") (pin "1") (pinfunction "1_1") (pintype "bidirectional"))
    )
    (net (code "71") (name "Net-(LED_PWR-PadA)") (class "Default")
      (node (ref "LED_PWR") (pin "A") (pinfunction "A_A") (pintype "passive"))
      (node (ref "R14") (pin "1") (pinfunction "1_1") (pintype "bidirectional"))
    )
    (net (code "72") (name "Net-(X1-D+)") (class "Default")
      (node (ref "R32") (pin "1") (pinfunction "1_1") (pintype "bidirectional"))
      (node (ref "X1") (pin "3") (pinfunction "D+_3") (pintype "bidirectional"))
    )
    (net (code "73") (name "Net-(X1-D-)") (class "Default")
      (node (ref "R31") (pin "1") (pinfunction "1_1") (pintype "bidirectional"))
      (node (ref "X1") (pin "2") (pinfunction "D-_2") (pintype "bidirectional"))
    )
    (net (code "74") (name "Net-(X1-GND1)") (class "Default")
      (node (ref "L1") (pin "2") (pinfunction "2_2") (pintype "passive"))
      (node (ref "X1") (pin "P$1") (pinfunction "GND1_P$1") (pintype "power_in"))
      (node (ref "X1") (pin "P$2") (pinfunction "GND2_P$2") (pintype "power_in"))
    )
    (net (code "75") (name "Net-(X1-VBUS)") (class "Default")
      (node (ref "L4") (pin "1") (pinfunction "1_1") (pintype "passive"))
      (node (ref "X1") (pin "1") (pinfunction "VBUS_1") (pintype "power_in"))
    )
    (net (code "76") (name "unconnected-(IC1-ADC0_DM0-Pad10)") (class "Default")
      (node (ref "IC1") (pin "10") (pinfunction "ADC0_DM0_10") (pintype "bidirectional"))
    )
    (net (code "77") (name "unconnected-(IC1-ADC0_DM3-Pad12)") (class "Default")
      (node (ref "IC1") (pin "12") (pinfunction "ADC0_DM3_12") (pintype "bidirectional"))
    )
    (net (code "78") (name "unconnected-(IC1-ADC0_DP0-Pad9)") (class "Default")
      (node (ref "IC1") (pin "9") (pinfunction "ADC0_DP0_9") (pintype "bidirectional"))
    )
    (net (code "79") (name "unconnected-(IC1-ADC0_DP3-Pad11)") (class "Default")
      (node (ref "IC1") (pin "11") (pinfunction "ADC0_DP3_11") (pintype "bidirectional"))
    )
    (net (code "80") (name "unconnected-(IC1-EXTAL32-Pad20)") (class "Default")
      (node (ref "IC1") (pin "20") (pinfunction "EXTAL32_20") (pintype "bidirectional"))
    )
    (net (code "81") (name "unconnected-(IC1-VREF_OUT-Pad17)") (class "Default")
      (node (ref "IC1") (pin "17") (pinfunction "VREF_OUT_17") (pintype "bidirectional"))
    )
    (net (code "82") (name "unconnected-(IC1-XTAL32-Pad19)") (class "Default")
      (node (ref "IC1") (pin "19") (pinfunction "XTAL32_19") (pintype "bidirectional"))
    )
    (net (code "83") (name "unconnected-(IC2-CLKOUT-PadP$2)") (class "Default")
      (node (ref "IC2") (pin "P$2") (pinfunction "CLKOUT_P$2") (pintype "output"))
    )
    (net (code "84") (name "unconnected-(IC2-MICBIAS-PadP$17)") (class "Default")
      (node (ref "IC2") (pin "P$17") (pinfunction "MICBIAS_P$17") (pintype "output"))
    )
    (net (code "85") (name "unconnected-(IC2-MICIN-PadP$18)") (class "Default")
      (node (ref "IC2") (pin "P$18") (pinfunction "MICIN_P$18") (pintype "input"))
    )
    (net (code "86") (name "unconnected-(SWD1-N{slash}C1-Pad7)") (class "Default")
      (node (ref "SWD1") (pin "7") (pinfunction "N/C1_7") (pintype "bidirectional"))
    )
  )
)
